# EAGLE_PCB_Design_Project1_1_DavidSalzman.net
KiCad netlist of a schematic drawn in EAGLE
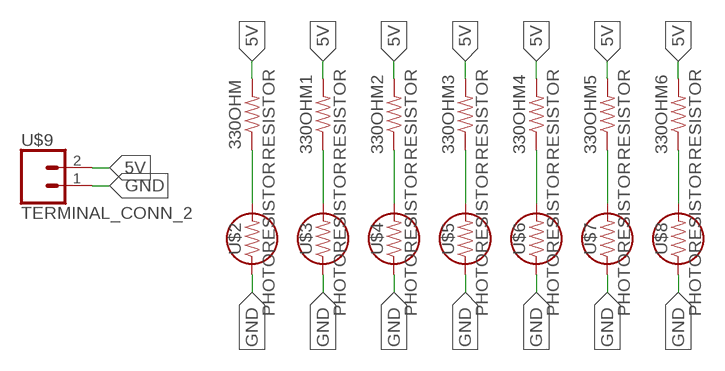
[diagram p0: schematic, sheet 1]

(export (version "E")
  (design (tool "Eeschema 10.0.6"))
  (components
    (comp (ref "330OHM")
      (value "RESISTOR")
      (footprint "eagle-import:RESISTOR")
      (libsource (lib "eagle-import") (part "RESISTOR"))
    )
    (comp (ref "330OHM1")
      (value "RESISTOR")
      (footprint "eagle-import:RESISTOR")
      (libsource (lib "eagle-import") (part "RESISTOR"))
    )
    (comp (ref "330OHM2")
      (value "RESISTOR")
      (footprint "eagle-import:RESISTOR")
      (libsource (lib "eagle-import") (part "RESISTOR"))
    )
    (comp (ref "330OHM3")
      (value "RESISTOR")
      (footprint "eagle-import:RESISTOR")
      (libsource (lib "eagle-import") (part "RESISTOR"))
    )
    (comp (ref "330OHM4")
      (value "RESISTOR")
      (footprint "eagle-import:RESISTOR")
      (libsource (lib "eagle-import") (part "RESISTOR"))
    )
    (comp (ref "330OHM5")
      (value "RESISTOR")
      (footprint "eagle-import:RESISTOR")
      (libsource (lib "eagle-import") (part "RESISTOR"))
    )
    (comp (ref "330OHM6")
      (value "RESISTOR")
      (footprint "eagle-import:RESISTOR")
      (libsource (lib "eagle-import") (part "RESISTOR"))
    )
    (comp (ref "U$2")
      (value "PHOTORESISTOR")
      (footprint "eagle-import:PHOTORESISTOR")
      (libsource (lib "eagle-import") (part "PHOTORESISTOR"))
    )
    (comp (ref "U$3")
      (value "PHOTORESISTOR")
      (footprint "eagle-import:PHOTORESISTOR")
      (libsource (lib "eagle-import") (part "PHOTORESISTOR"))
    )
    (comp (ref "U$4")
      (value "PHOTORESISTOR")
      (footprint "eagle-import:PHOTORESISTOR")
      (libsource (lib "eagle-import") (part "PHOTORESISTOR"))
    )
    (comp (ref "U$5")
      (value "PHOTORESISTOR")
      (footprint "eagle-import:PHOTORESISTOR")
      (libsource (lib "eagle-import") (part "PHOTORESISTOR"))
    )
    (comp (ref "U$6")
      (value "PHOTORESISTOR")
      (footprint "eagle-import:PHOTORESISTOR")
      (libsource (lib "eagle-import") (part "PHOTORESISTOR"))
    )
    (comp (ref "U$7")
      (value "PHOTORESISTOR")
      (footprint "eagle-import:PHOTORESISTOR")
      (libsource (lib "eagle-import") (part "PHOTORESISTOR"))
    )
    (comp (ref "U$8")
      (value "PHOTORESISTOR")
      (footprint "eagle-import:PHOTORESISTOR")
      (libsource (lib "eagle-import") (part "PHOTORESISTOR"))
    )
    (comp (ref "U$9")
      (value "TERMINAL_CONN_2")
      (footprint "eagle-import:TERMINAL_CONN_2")
      (libsource (lib "eagle-import") (part "TERMINAL_CONN_2"))
    )
  )
  (nets
    (net (code "1") (name "5V") (class "Default")
      (node (ref "330OHM") (pin "2") (pinfunction "2_2") (pintype "passive"))
      (node (ref "330OHM1") (pin "2") (pinfunction "2_2") (pintype "passive"))
      (node (ref "330OHM2") (pin "2") (pinfunction "2_2") (pintype "passive"))
      (node (ref "330OHM3") (pin "2") (pinfunction "2_2") (pintype "passive"))
      (node (ref "330OHM4") (pin "2") (pinfunction "2_2") (pintype "passive"))
      (node (ref "330OHM5") (pin "2") (pinfunction "2_2") (pintype "passive"))
      (node (ref "330OHM6") (pin "2") (pinfunction "2_2") (pintype "passive"))
      (node (ref "U$9") (pin "2") (pinfunction "2_2") (pintype "passive"))
    )
    (net (code "2") (name "GND") (class "Default")
      (node (ref "U$2") (pin "P$1") (pinfunction "1_P$1") (pintype "passive"))
      (node (ref "U$3") (pin "P$1") (pinfunction "1_P$1") (pintype "passive"))
      (node (ref "U$4") (pin "P$1") (pinfunction "1_P$1") (pintype "passive"))
      (node (ref "U$5") (pin "P$1") (pinfunction "1_P$1") (pintype "passive"))
      (node (ref "U$6") (pin "P$1") (pinfunction "1_P$1") (pintype "passive"))
      (node (ref "U$7") (pin "P$1") (pinfunction "1_P$1") (pintype "passive"))
      (node (ref "U$8") (pin "P$1") (pinfunction "1_P$1") (pintype "passive"))
      (node (ref "U$9") (pin "1") (pinfunction "1_1") (pintype "passive"))
    )
    (net (code "3") (name "Net-(U$2-2)") (class "Default")
      (node (ref "330OHM") (pin "1") (pinfunction "1_1") (pintype "passive"))
      (node (ref "U$2") (pin "P$2") (pinfunction "2_P$2") (pintype "passive"))
    )
    (net (code "4") (name "Net-(U$3-2)") (class "Default")
      (node (ref "330OHM1") (pin "1") (pinfunction "1_1") (pintype "passive"))
      (node (ref "U$3") (pin "P$2") (pinfunction "2_P$2") (pintype "passive"))
    )
    (net (code "5") (name "Net-(U$4-2)") (class "Default")
      (node (ref "330OHM2") (pin "1") (pinfunction "1_1") (pintype "passive"))
      (node (ref "U$4") (pin "P$2") (pinfunction "2_P$2") (pintype "passive"))
    )
    (net (code "6") (name "Net-(U$5-2)") (class "Default")
      (node (ref "330OHM3") (pin "1") (pinfunction "1_1") (pintype "passive"))
      (node (ref "U$5") (pin "P$2") (pinfunction "2_P$2") (pintype "passive"))
    )
    (net (code "7") (name "Net-(U$6-2)") (class "Default")
      (node (ref "330OHM4") (pin "1") (pinfunction "1_1") (pintype "passive"))
      (node (ref "U$6") (pin "P$2") (pinfunction "2_P$2") (pintype "passive"))
    )
    (net (code "8") (name "Net-(U$7-2)") (class "Default")
      (node (ref "330OHM5") (pin "1") (pinfunction "1_1") (pintype "passive"))
      (node (ref "U$7") (pin "P$2") (pinfunction "2_P$2") (pintype "passive"))
    )
    (net (code "9") (name "Net-(U$8-2)") (class "Default")
      (node (ref "330OHM6") (pin "1") (pinfunction "1_1") (pintype "passive"))
      (node (ref "U$8") (pin "P$2") (pinfunction "2_P$2") (pintype "passive"))
    )
  )
)
